# S7CAS-PLEIADES-CARTE-MERE_Pxx_FPGA_bank0.net
KiCad netlist of a schematic drawn in Altium Designer
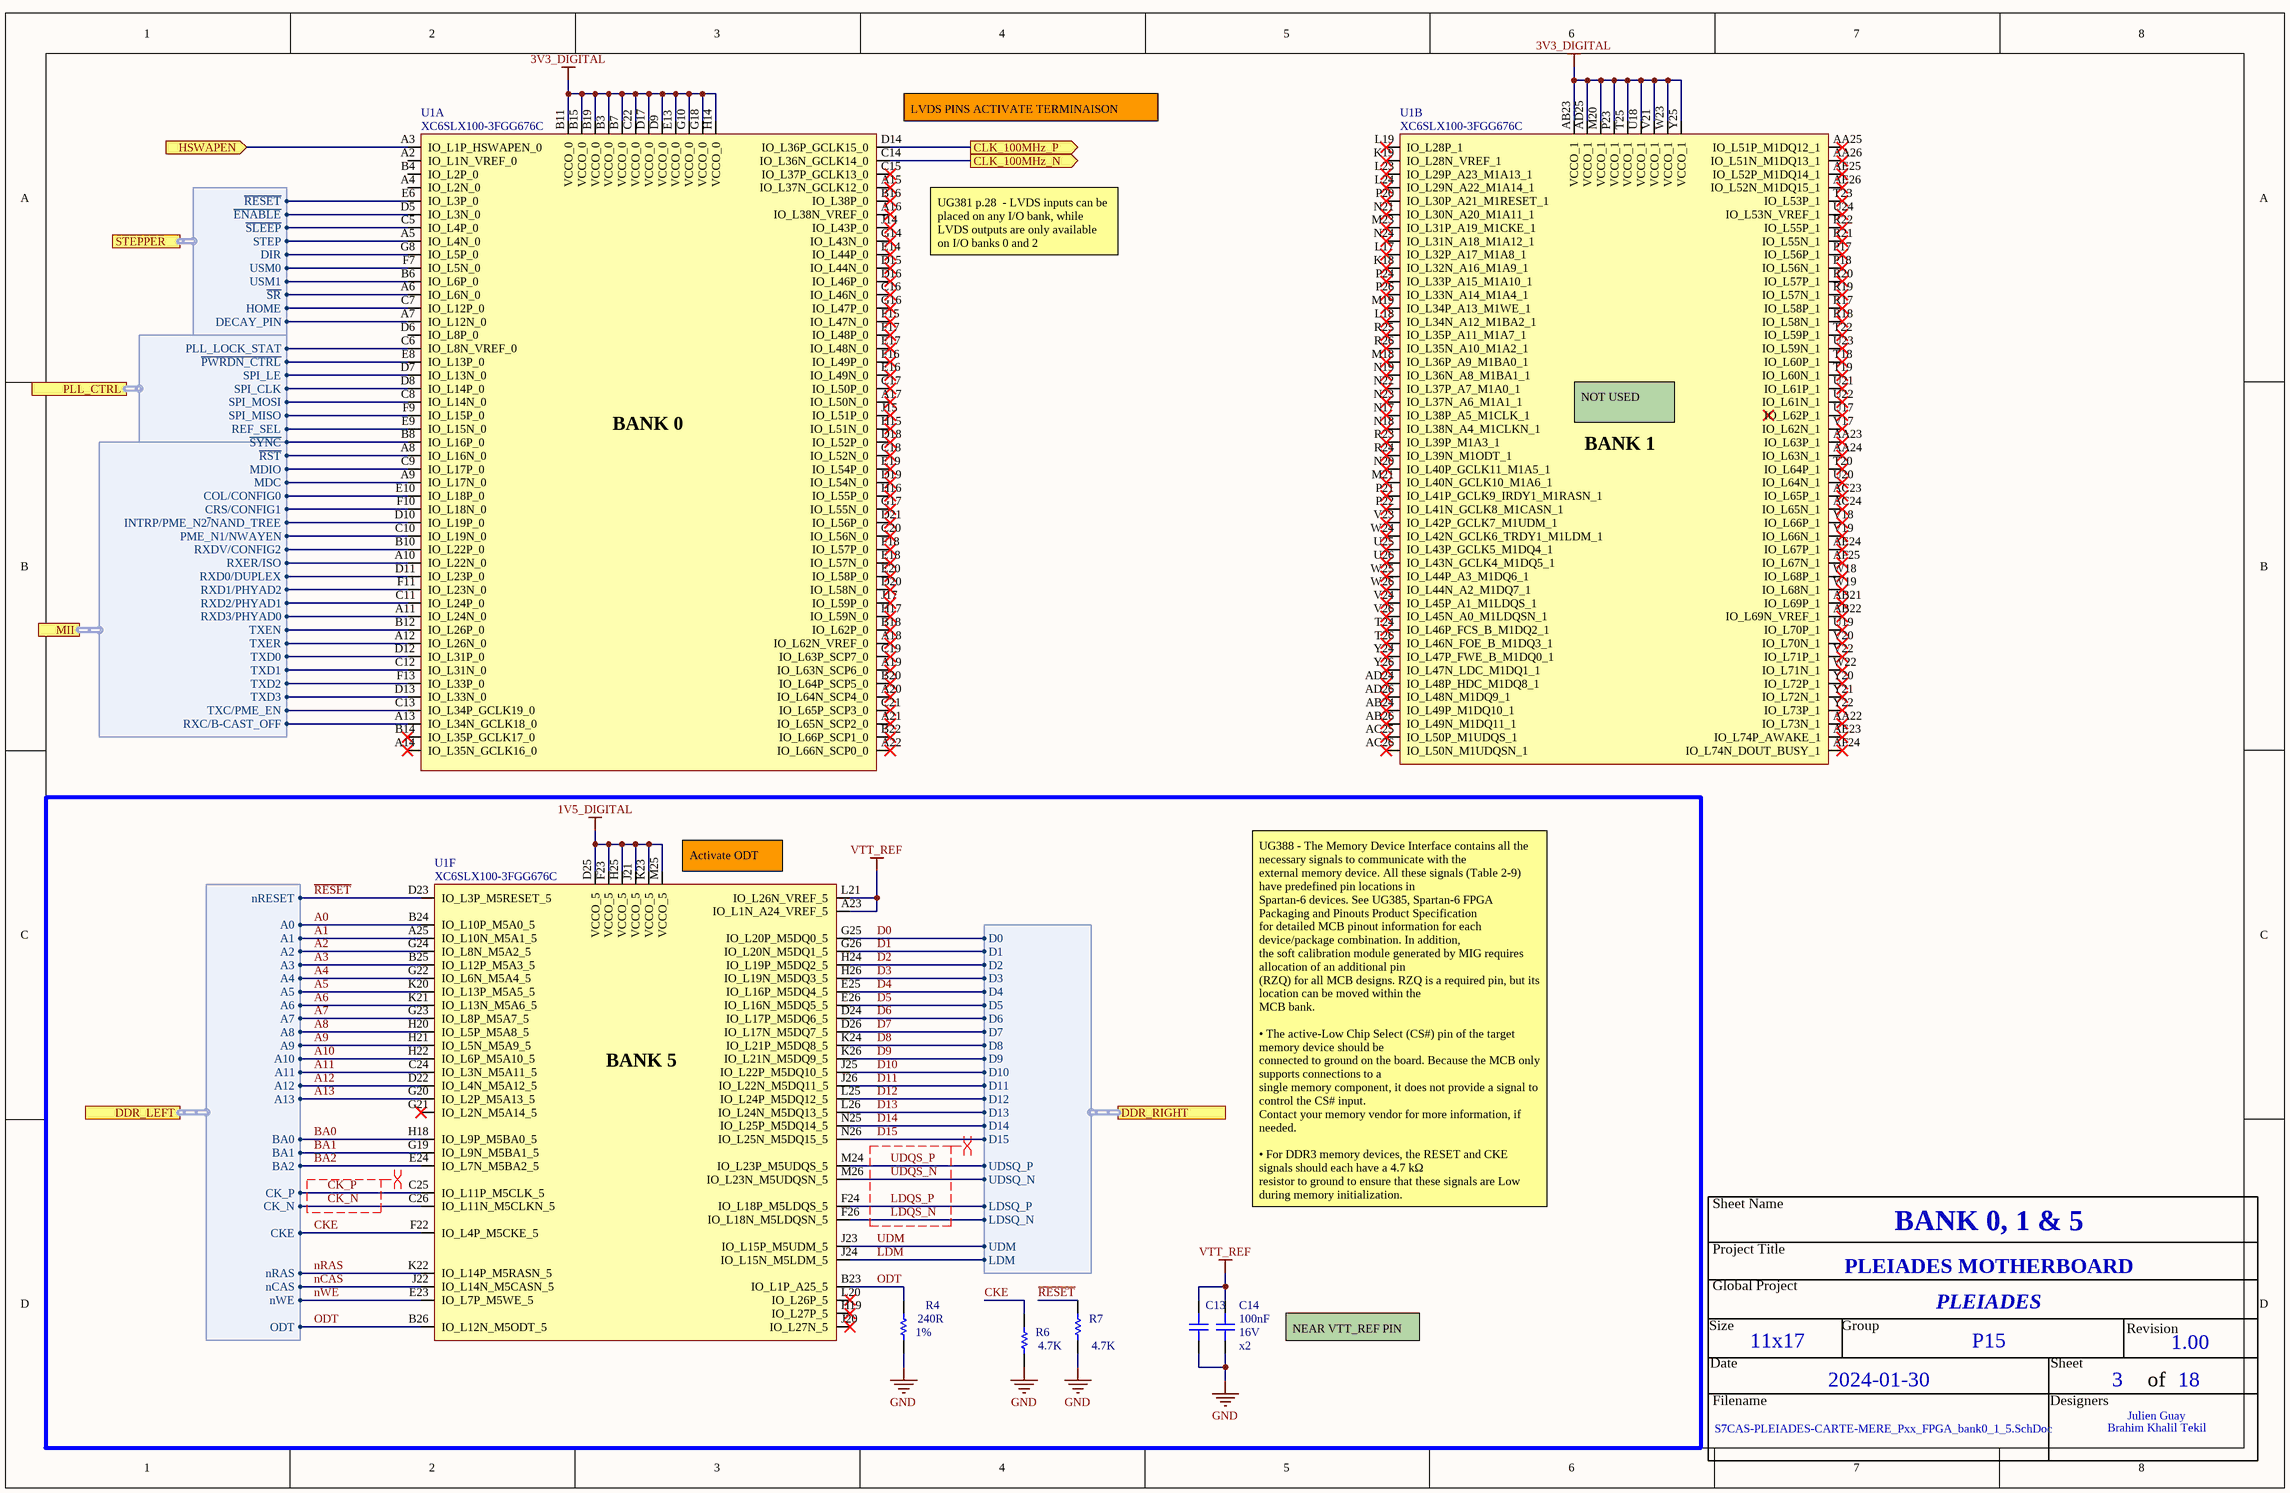
[diagram p0: S7CAS-PLEIADES-CARTE-MERE_Pxx_FPGA_bank0_1_5.SchDoc]

(export (version "E")
  (design (tool "Eeschema 10.0.6"))
  (components
    (comp (ref "C13")
      (value "CAP - 0603")
      (footprint "CAP_0603")
      (fields (field (name "VOLTAGE") "16V") (field (name "CREATEDBY") "Jonathan Bouchard"))
      (libsource (lib "S7CAS_LIB2023") (part "CAP - 0603"))
    )
    (comp (ref "C14")
      (value "100nF")
      (footprint "CAP_0603")
      (description "CAP - 0603")
      (fields (field (name "VOLTAGE") "16V") (field (name "CREATEDBY") "Jonathan Bouchard"))
      (libsource (lib "S7CAS_LIB2023") (part "CAP - 0603"))
    )
    (comp (ref "R4")
      (value "240R")
      (footprint "RES_0603")
      (description "RES - 0603")
      (fields (field (name "PRECISION") "1%") (field (name "CREATEDBY") "Jonathan Bouchard"))
      (libsource (lib "S7CAS_LIB2023") (part "RES - 0603"))
    )
    (comp (ref "R6")
      (value "4.7K")
      (footprint "RES_0603")
      (description "RES - 0603")
      (fields (field (name "CREATEDBY") "Jonathan Bouchard"))
      (libsource (lib "S7CAS_LIB2023") (part "RES - 0603"))
    )
    (comp (ref "R7")
      (value "4.7K")
      (footprint "RES_0603")
      (description "RES - 0603")
      (fields (field (name "CREATEDBY") "Jonathan Bouchard"))
      (libsource (lib "S7CAS_LIB2023") (part "RES - 0603"))
    )
    (comp (ref "U1")
      (value "XC6SLX100-3FGG676C")
      (footprint "FPGA_XILINX_FGG676")
      (description "FPGA - XILINX SPARTAN 6 480 I/O - BGA-676")
      (fields
        (field (name "VOLTAGE") "1.14 V ~ 1.26 V")
        (field (name "MFG") "Xilinx")
        (field (name "CREATEDBY") "Jonathan Bouchard")
      )
      (libsource (lib "S7CAS_LIB2023") (part "FPGA_XC6SLX100-3FGG676C"))
    )
  )
  (nets
    (net (code "9") (name "/A0") (class "Default")
      (node (ref "U1") (pin "B24") (pinfunction "IO_L10P_M5A0_5_B24") (pintype "passive"))
    )
    (net (code "10") (name "/A1") (class "Default")
      (node (ref "U1") (pin "A25") (pinfunction "IO_L10N_M5A1_5_A25") (pintype "passive"))
    )
    (net (code "11") (name "/A2") (class "Default")
      (node (ref "U1") (pin "G24") (pinfunction "IO_L8N_M5A2_5_G24") (pintype "passive"))
    )
    (net (code "12") (name "/A3") (class "Default")
      (node (ref "U1") (pin "B25") (pinfunction "IO_L12P_M5A3_5_B25") (pintype "passive"))
    )
    (net (code "13") (name "/A4") (class "Default")
      (node (ref "U1") (pin "G22") (pinfunction "IO_L6N_M5A4_5_G22") (pintype "passive"))
    )
    (net (code "14") (name "/A5") (class "Default")
      (node (ref "U1") (pin "K20") (pinfunction "IO_L13P_M5A5_5_K20") (pintype "passive"))
    )
    (net (code "15") (name "/A6") (class "Default")
      (node (ref "U1") (pin "K21") (pinfunction "IO_L13N_M5A6_5_K21") (pintype "passive"))
    )
    (net (code "16") (name "/A7") (class "Default")
      (node (ref "U1") (pin "G23") (pinfunction "IO_L8P_M5A7_5_G23") (pintype "passive"))
    )
    (net (code "17") (name "/A8") (class "Default")
      (node (ref "U1") (pin "H20") (pinfunction "IO_L5P_M5A8_5_H20") (pintype "passive"))
    )
    (net (code "18") (name "/A9") (class "Default")
      (node (ref "U1") (pin "H21") (pinfunction "IO_L5N_M5A9_5_H21") (pintype "passive"))
    )
    (net (code "19") (name "/A10") (class "Default")
      (node (ref "U1") (pin "H22") (pinfunction "IO_L6P_M5A10_5_H22") (pintype "passive"))
    )
    (net (code "20") (name "/A11") (class "Default")
      (node (ref "U1") (pin "C24") (pinfunction "IO_L3N_M5A11_5_C24") (pintype "passive"))
    )
    (net (code "21") (name "/A12") (class "Default")
      (node (ref "U1") (pin "D22") (pinfunction "IO_L4N_M5A12_5_D22") (pintype "passive"))
    )
    (net (code "22") (name "/A13") (class "Default")
      (node (ref "U1") (pin "G20") (pinfunction "IO_L2P_M5A13_5_G20") (pintype "passive"))
    )
    (net (code "23") (name "/BA0") (class "Default")
      (node (ref "U1") (pin "H18") (pinfunction "IO_L9P_M5BA0_5_H18") (pintype "passive"))
    )
    (net (code "24") (name "/BA1") (class "Default")
      (node (ref "U1") (pin "G19") (pinfunction "IO_L9N_M5BA1_5_G19") (pintype "passive"))
    )
    (net (code "25") (name "/BA2") (class "Default")
      (node (ref "U1") (pin "E24") (pinfunction "IO_L7N_M5BA2_5_E24") (pintype "passive"))
    )
    (net (code "26") (name "/CKE") (class "Default")
      (node (ref "R6") (pin "2") (pinfunction "2_2") (pintype "passive"))
      (node (ref "U1") (pin "F22") (pinfunction "IO_L4P_M5CKE_5_F22") (pintype "passive"))
    )
    (net (code "27") (name "/CK_N") (class "Default")
      (node (ref "U1") (pin "C26") (pinfunction "IO_L11N_M5CLKN_5_C26") (pintype "passive"))
    )
    (net (code "28") (name "/CK_P") (class "Default")
      (node (ref "U1") (pin "C25") (pinfunction "IO_L11P_M5CLK_5_C25") (pintype "passive"))
    )
    (net (code "29") (name "/CLK_100MHz_N") (class "Default")
      (node (ref "U1") (pin "C14") (pinfunction "IO_L36N_GCLK14_0_C14") (pintype "passive"))
    )
    (net (code "30") (name "/CLK_100MHz_P") (class "Default")
      (node (ref "U1") (pin "D14") (pinfunction "IO_L36P_GCLK15_0_D14") (pintype "passive"))
    )
    (net (code "31") (name "/D0") (class "Default")
      (node (ref "U1") (pin "G25") (pinfunction "IO_L20P_M5DQ0_5_G25") (pintype "passive"))
    )
    (net (code "32") (name "/D1") (class "Default")
      (node (ref "U1") (pin "G26") (pinfunction "IO_L20N_M5DQ1_5_G26") (pintype "passive"))
    )
    (net (code "33") (name "/D2") (class "Default")
      (node (ref "U1") (pin "H24") (pinfunction "IO_L19P_M5DQ2_5_H24") (pintype "passive"))
    )
    (net (code "34") (name "/D3") (class "Default")
      (node (ref "U1") (pin "H26") (pinfunction "IO_L19N_M5DQ3_5_H26") (pintype "passive"))
    )
    (net (code "35") (name "/D4") (class "Default")
      (node (ref "U1") (pin "E25") (pinfunction "IO_L16P_M5DQ4_5_E25") (pintype "passive"))
    )
    (net (code "36") (name "/D5") (class "Default")
      (node (ref "U1") (pin "E26") (pinfunction "IO_L16N_M5DQ5_5_E26") (pintype "passive"))
    )
    (net (code "37") (name "/D6") (class "Default")
      (node (ref "U1") (pin "D24") (pinfunction "IO_L17P_M5DQ6_5_D24") (pintype "passive"))
    )
    (net (code "38") (name "/D7") (class "Default")
      (node (ref "U1") (pin "D26") (pinfunction "IO_L17N_M5DQ7_5_D26") (pintype "passive"))
    )
    (net (code "39") (name "/D8") (class "Default")
      (node (ref "U1") (pin "K24") (pinfunction "IO_L21P_M5DQ8_5_K24") (pintype "passive"))
    )
    (net (code "40") (name "/D9") (class "Default")
      (node (ref "U1") (pin "K26") (pinfunction "IO_L21N_M5DQ9_5_K26") (pintype "passive"))
    )
    (net (code "41") (name "/D10") (class "Default")
      (node (ref "U1") (pin "J25") (pinfunction "IO_L22P_M5DQ10_5_J25") (pintype "passive"))
    )
    (net (code "42") (name "/D11") (class "Default")
      (node (ref "U1") (pin "J26") (pinfunction "IO_L22N_M5DQ11_5_J26") (pintype "passive"))
    )
    (net (code "43") (name "/D12") (class "Default")
      (node (ref "U1") (pin "L25") (pinfunction "IO_L24P_M5DQ12_5_L25") (pintype "passive"))
    )
    (net (code "44") (name "/D13") (class "Default")
      (node (ref "U1") (pin "L26") (pinfunction "IO_L24N_M5DQ13_5_L26") (pintype "passive"))
    )
    (net (code "45") (name "/D14") (class "Default")
      (node (ref "U1") (pin "N25") (pinfunction "IO_L25P_M5DQ14_5_N25") (pintype "passive"))
    )
    (net (code "46") (name "/D15") (class "Default")
      (node (ref "U1") (pin "N26") (pinfunction "IO_L25N_M5DQ15_5_N26") (pintype "passive"))
    )
    (net (code "47") (name "/HSWAPEN") (class "Default")
      (node (ref "U1") (pin "A3") (pinfunction "IO_L1P_HSWAPEN_0_A3") (pintype "passive"))
    )
    (net (code "48") (name "/LDM") (class "Default")
      (node (ref "U1") (pin "J24") (pinfunction "IO_L15N_M5LDM_5_J24") (pintype "passive"))
    )
    (net (code "49") (name "/LDQS_N") (class "Default")
      (node (ref "U1") (pin "F26") (pinfunction "IO_L18N_M5LDQSN_5_F26") (pintype "passive"))
    )
    (net (code "50") (name "/LDQS_P") (class "Default")
      (node (ref "U1") (pin "F24") (pinfunction "IO_L18P_M5LDQS_5_F24") (pintype "passive"))
    )
    (net (code "51") (name "/ODT") (class "Default")
      (node (ref "R4") (pin "2") (pinfunction "2_2") (pintype "passive"))
      (node (ref "U1") (pin "B23") (pinfunction "IO_L1P_A25_5_B23") (pintype "passive"))
      (node (ref "U1") (pin "B26") (pinfunction "IO_L12N_M5ODT_5_B26") (pintype "passive"))
    )
    (net (code "53") (name "/RESET") (class "Default")
      (node (ref "R7") (pin "2") (pinfunction "2_2") (pintype "passive"))
      (node (ref "U1") (pin "D23") (pinfunction "IO_L3P_M5RESET_5_D23") (pintype "passive"))
    )
    (net (code "55") (name "/UDM") (class "Default")
      (node (ref "U1") (pin "J23") (pinfunction "IO_L15P_M5UDM_5_J23") (pintype "passive"))
    )
    (net (code "56") (name "/UDQS_N") (class "Default")
      (node (ref "U1") (pin "M26") (pinfunction "IO_L23N_M5UDQSN_5_M26") (pintype "passive"))
    )
    (net (code "57") (name "/UDQS_P") (class "Default")
      (node (ref "U1") (pin "M24") (pinfunction "IO_L23P_M5UDQS_5_M24") (pintype "passive"))
    )
    (net (code "58") (name "/nCAS") (class "Default")
      (node (ref "U1") (pin "J22") (pinfunction "IO_L14N_M5CASN_5_J22") (pintype "passive"))
    )
    (net (code "59") (name "/nRAS") (class "Default")
      (node (ref "U1") (pin "K22") (pinfunction "IO_L14P_M5RASN_5_K22") (pintype "passive"))
    )
    (net (code "60") (name "/nWE") (class "Default")
      (node (ref "U1") (pin "E23") (pinfunction "IO_L7P_M5WE_5_E23") (pintype "passive"))
    )
    (net (code "64") (name "1V5_DIGITAL") (class "Default")
      (node (ref "U1") (pin "D25") (pinfunction "VCCO_5_D25") (pintype "passive"))
      (node (ref "U1") (pin "F23") (pinfunction "VCCO_5_F23") (pintype "passive"))
      (node (ref "U1") (pin "H25") (pinfunction "VCCO_5_H25") (pintype "passive"))
      (node (ref "U1") (pin "J21") (pinfunction "VCCO_5_J21") (pintype "passive"))
      (node (ref "U1") (pin "K23") (pinfunction "VCCO_5_K23") (pintype "passive"))
      (node (ref "U1") (pin "M25") (pinfunction "VCCO_5_M25") (pintype "passive"))
    )
    (net (code "65") (name "3V3_DIGITAL") (class "Default")
      (node (ref "U1") (pin "AB23") (pinfunction "VCCO_1_AB23") (pintype "passive"))
      (node (ref "U1") (pin "AD25") (pinfunction "VCCO_1_AD25") (pintype "passive"))
      (node (ref "U1") (pin "B11") (pinfunction "VCCO_0_B11") (pintype "passive"))
      (node (ref "U1") (pin "B15") (pinfunction "VCCO_0_B15") (pintype "passive"))
      (node (ref "U1") (pin "B19") (pinfunction "VCCO_0_B19") (pintype "passive"))
      (node (ref "U1") (pin "B3") (pinfunction "VCCO_0_B3") (pintype "passive"))
      (node (ref "U1") (pin "B7") (pinfunction "VCCO_0_B7") (pintype "passive"))
      (node (ref "U1") (pin "C22") (pinfunction "VCCO_0_C22") (pintype "passive"))
      (node (ref "U1") (pin "D17") (pinfunction "VCCO_0_D17") (pintype "passive"))
      (node (ref "U1") (pin "D9") (pinfunction "VCCO_0_D9") (pintype "passive"))
      (node (ref "U1") (pin "E13") (pinfunction "VCCO_0_E13") (pintype "passive"))
      (node (ref "U1") (pin "G10") (pinfunction "VCCO_0_G10") (pintype "passive"))
      (node (ref "U1") (pin "G18") (pinfunction "VCCO_0_G18") (pintype "passive"))
      (node (ref "U1") (pin "H14") (pinfunction "VCCO_0_H14") (pintype "passive"))
      (node (ref "U1") (pin "M20") (pinfunction "VCCO_1_M20") (pintype "passive"))
      (node (ref "U1") (pin "P23") (pinfunction "VCCO_1_P23") (pintype "passive"))
      (node (ref "U1") (pin "T25") (pinfunction "VCCO_1_T25") (pintype "passive"))
      (node (ref "U1") (pin "U18") (pinfunction "VCCO_1_U18") (pintype "passive"))
      (node (ref "U1") (pin "V21") (pinfunction "VCCO_1_V21") (pintype "passive"))
      (node (ref "U1") (pin "W23") (pinfunction "VCCO_1_W23") (pintype "passive"))
      (node (ref "U1") (pin "Y25") (pinfunction "VCCO_1_Y25") (pintype "passive"))
    )
    (net (code "66") (name "GND") (class "Default")
      (node (ref "C13") (pin "1") (pinfunction "1_1") (pintype "passive"))
      (node (ref "C14") (pin "1") (pinfunction "1_1") (pintype "passive"))
      (node (ref "R4") (pin "1") (pinfunction "1_1") (pintype "passive"))
      (node (ref "R6") (pin "1") (pinfunction "1_1") (pintype "passive"))
      (node (ref "R7") (pin "1") (pinfunction "1_1") (pintype "passive"))
    )
    (net (code "67") (name "VTT_REF") (class "Default")
      (node (ref "C13") (pin "2") (pinfunction "2_2") (pintype "passive"))
      (node (ref "C14") (pin "2") (pinfunction "2_2") (pintype "passive"))
      (node (ref "U1") (pin "A23") (pinfunction "IO_L1N_A24_VREF_5_A23") (pintype "passive"))
      (node (ref "U1") (pin "L21") (pinfunction "IO_L26N_VREF_5_L21") (pintype "passive"))
    )
    (net (code "68") (name "unconnected-(U1A-IO_L1N_VREF_0-PadA2)") (class "Default")
      (node (ref "U1") (pin "A2") (pinfunction "IO_L1N_VREF_0_A2") (pintype "passive"))
    )
    (net (code "69") (name "unconnected-(U1A-IO_L2N_0-PadA4)") (class "Default")
      (node (ref "U1") (pin "A4") (pinfunction "IO_L2N_0_A4") (pintype "passive"))
    )
    (net (code "70") (name "unconnected-(U1A-IO_L2P_0-PadB4)") (class "Default")
      (node (ref "U1") (pin "B4") (pinfunction "IO_L2P_0_B4") (pintype "passive"))
    )
    (net (code "71") (name "unconnected-(U1A-IO_L3N_0-PadD5)") (class "Default")
      (node (ref "U1") (pin "D5") (pinfunction "IO_L3N_0_D5") (pintype "passive"))
    )
    (net (code "72") (name "unconnected-(U1A-IO_L3P_0-PadE6)") (class "Default")
      (node (ref "U1") (pin "E6") (pinfunction "IO_L3P_0_E6") (pintype "passive"))
    )
    (net (code "73") (name "unconnected-(U1A-IO_L4N_0-PadA5)") (class "Default")
      (node (ref "U1") (pin "A5") (pinfunction "IO_L4N_0_A5") (pintype "passive"))
    )
    (net (code "74") (name "unconnected-(U1A-IO_L4P_0-PadC5)") (class "Default")
      (node (ref "U1") (pin "C5") (pinfunction "IO_L4P_0_C5") (pintype "passive"))
    )
    (net (code "75") (name "unconnected-(U1A-IO_L5N_0-PadF7)") (class "Default")
      (node (ref "U1") (pin "F7") (pinfunction "IO_L5N_0_F7") (pintype "passive"))
    )
    (net (code "76") (name "unconnected-(U1A-IO_L5P_0-PadG8)") (class "Default")
      (node (ref "U1") (pin "G8") (pinfunction "IO_L5P_0_G8") (pintype "passive"))
    )
    (net (code "77") (name "unconnected-(U1A-IO_L6N_0-PadA6)") (class "Default")
      (node (ref "U1") (pin "A6") (pinfunction "IO_L6N_0_A6") (pintype "passive"))
    )
    (net (code "78") (name "unconnected-(U1A-IO_L6P_0-PadB6)") (class "Default")
      (node (ref "U1") (pin "B6") (pinfunction "IO_L6P_0_B6") (pintype "passive"))
    )
    (net (code "79") (name "unconnected-(U1A-IO_L8N_VREF_0-PadC6)") (class "Default")
      (node (ref "U1") (pin "C6") (pinfunction "IO_L8N_VREF_0_C6") (pintype "passive"))
    )
    (net (code "80") (name "unconnected-(U1A-IO_L8P_0-PadD6)") (class "Default")
      (node (ref "U1") (pin "D6") (pinfunction "IO_L8P_0_D6") (pintype "passive"))
    )
    (net (code "81") (name "unconnected-(U1A-IO_L12N_0-PadA7)") (class "Default")
      (node (ref "U1") (pin "A7") (pinfunction "IO_L12N_0_A7") (pintype "passive"))
    )
    (net (code "82") (name "unconnected-(U1A-IO_L12P_0-PadC7)") (class "Default")
      (node (ref "U1") (pin "C7") (pinfunction "IO_L12P_0_C7") (pintype "passive"))
    )
    (net (code "83") (name "unconnected-(U1A-IO_L13N_0-PadD7)") (class "Default")
      (node (ref "U1") (pin "D7") (pinfunction "IO_L13N_0_D7") (pintype "passive"))
    )
    (net (code "84") (name "unconnected-(U1A-IO_L13P_0-PadE8)") (class "Default")
      (node (ref "U1") (pin "E8") (pinfunction "IO_L13P_0_E8") (pintype "passive"))
    )
    (net (code "85") (name "unconnected-(U1A-IO_L14N_0-PadC8)") (class "Default")
      (node (ref "U1") (pin "C8") (pinfunction "IO_L14N_0_C8") (pintype "passive"))
    )
    (net (code "86") (name "unconnected-(U1A-IO_L14P_0-PadD8)") (class "Default")
      (node (ref "U1") (pin "D8") (pinfunction "IO_L14P_0_D8") (pintype "passive"))
    )
    (net (code "87") (name "unconnected-(U1A-IO_L15N_0-PadE9)") (class "Default")
      (node (ref "U1") (pin "E9") (pinfunction "IO_L15N_0_E9") (pintype "passive"))
    )
    (net (code "88") (name "unconnected-(U1A-IO_L15P_0-PadF9)") (class "Default")
      (node (ref "U1") (pin "F9") (pinfunction "IO_L15P_0_F9") (pintype "passive"))
    )
    (net (code "89") (name "unconnected-(U1A-IO_L16N_0-PadA8)") (class "Default")
      (node (ref "U1") (pin "A8") (pinfunction "IO_L16N_0_A8") (pintype "passive"))
    )
    (net (code "90") (name "unconnected-(U1A-IO_L16P_0-PadB8)") (class "Default")
      (node (ref "U1") (pin "B8") (pinfunction "IO_L16P_0_B8") (pintype "passive"))
    )
    (net (code "91") (name "unconnected-(U1A-IO_L17N_0-PadA9)") (class "Default")
      (node (ref "U1") (pin "A9") (pinfunction "IO_L17N_0_A9") (pintype "passive"))
    )
    (net (code "92") (name "unconnected-(U1A-IO_L17P_0-PadC9)") (class "Default")
      (node (ref "U1") (pin "C9") (pinfunction "IO_L17P_0_C9") (pintype "passive"))
    )
    (net (code "93") (name "unconnected-(U1A-IO_L18N_0-PadF10)") (class "Default")
      (node (ref "U1") (pin "F10") (pinfunction "IO_L18N_0_F10") (pintype "passive"))
    )
    (net (code "94") (name "unconnected-(U1A-IO_L18P_0-PadE10)") (class "Default")
      (node (ref "U1") (pin "E10") (pinfunction "IO_L18P_0_E10") (pintype "passive"))
    )
    (net (code "95") (name "unconnected-(U1A-IO_L19N_0-PadC10)") (class "Default")
      (node (ref "U1") (pin "C10") (pinfunction "IO_L19N_0_C10") (pintype "passive"))
    )
    (net (code "96") (name "unconnected-(U1A-IO_L19P_0-PadD10)") (class "Default")
      (node (ref "U1") (pin "D10") (pinfunction "IO_L19P_0_D10") (pintype "passive"))
    )
    (net (code "97") (name "unconnected-(U1A-IO_L22N_0-PadA10)") (class "Default")
      (node (ref "U1") (pin "A10") (pinfunction "IO_L22N_0_A10") (pintype "passive"))
    )
    (net (code "98") (name "unconnected-(U1A-IO_L22P_0-PadB10)") (class "Default")
      (node (ref "U1") (pin "B10") (pinfunction "IO_L22P_0_B10") (pintype "passive"))
    )
    (net (code "99") (name "unconnected-(U1A-IO_L23N_0-PadF11)") (class "Default")
      (node (ref "U1") (pin "F11") (pinfunction "IO_L23N_0_F11") (pintype "passive"))
    )
    (net (code "100") (name "unconnected-(U1A-IO_L23P_0-PadD11)") (class "Default")
      (node (ref "U1") (pin "D11") (pinfunction "IO_L23P_0_D11") (pintype "passive"))
    )
    (net (code "101") (name "unconnected-(U1A-IO_L24N_0-PadA11)") (class "Default")
      (node (ref "U1") (pin "A11") (pinfunction "IO_L24N_0_A11") (pintype "passive"))
    )
    (net (code "102") (name "unconnected-(U1A-IO_L24P_0-PadC11)") (class "Default")
      (node (ref "U1") (pin "C11") (pinfunction "IO_L24P_0_C11") (pintype "passive"))
    )
    (net (code "103") (name "unconnected-(U1A-IO_L26N_0-PadA12)") (class "Default")
      (node (ref "U1") (pin "A12") (pinfunction "IO_L26N_0_A12") (pintype "passive"))
    )
    (net (code "104") (name "unconnected-(U1A-IO_L26P_0-PadB12)") (class "Default")
      (node (ref "U1") (pin "B12") (pinfunction "IO_L26P_0_B12") (pintype "passive"))
    )
    (net (code "105") (name "unconnected-(U1A-IO_L31N_0-PadC12)") (class "Default")
      (node (ref "U1") (pin "C12") (pinfunction "IO_L31N_0_C12") (pintype "passive"))
    )
    (net (code "106") (name "unconnected-(U1A-IO_L31P_0-PadD12)") (class "Default")
      (node (ref "U1") (pin "D12") (pinfunction "IO_L31P_0_D12") (pintype "passive"))
    )
    (net (code "107") (name "unconnected-(U1A-IO_L33N_0-PadD13)") (class "Default")
      (node (ref "U1") (pin "D13") (pinfunction "IO_L33N_0_D13") (pintype "passive"))
    )
    (net (code "108") (name "unconnected-(U1A-IO_L33P_0-PadF13)") (class "Default")
      (node (ref "U1") (pin "F13") (pinfunction "IO_L33P_0_F13") (pintype "passive"))
    )
    (net (code "109") (name "unconnected-(U1A-IO_L34N_GCLK18_0-PadA13)") (class "Default")
      (node (ref "U1") (pin "A13") (pinfunction "IO_L34N_GCLK18_0_A13") (pintype "passive"))
    )
    (net (code "110") (name "unconnected-(U1A-IO_L34P_GCLK19_0-PadC13)") (class "Default")
      (node (ref "U1") (pin "C13") (pinfunction "IO_L34P_GCLK19_0_C13") (pintype "passive"))
    )
    (net (code "111") (name "unconnected-(U1A-IO_L35N_GCLK16_0-PadA14)") (class "Default")
      (node (ref "U1") (pin "A14") (pinfunction "IO_L35N_GCLK16_0_A14") (pintype "passive+no_connect"))
    )
    (net (code "112") (name "unconnected-(U1A-IO_L35P_GCLK17_0-PadB14)") (class "Default")
      (node (ref "U1") (pin "B14") (pinfunction "IO_L35P_GCLK17_0_B14") (pintype "passive+no_connect"))
    )
    (net (code "113") (name "unconnected-(U1A-IO_L37N_GCLK12_0-PadA15)") (class "Default")
      (node (ref "U1") (pin "A15") (pinfunction "IO_L37N_GCLK12_0_A15") (pintype "passive+no_connect"))
    )
    (net (code "114") (name "unconnected-(U1A-IO_L37P_GCLK13_0-PadC15)") (class "Default")
      (node (ref "U1") (pin "C15") (pinfunction "IO_L37P_GCLK13_0_C15") (pintype "passive+no_connect"))
    )
    (net (code "115") (name "unconnected-(U1A-IO_L38N_VREF_0-PadA16)") (class "Default")
      (node (ref "U1") (pin "A16") (pinfunction "IO_L38N_VREF_0_A16") (pintype "passive+no_connect"))
    )
    (net (code "116") (name "unconnected-(U1A-IO_L38P_0-PadB16)") (class "Default")
      (node (ref "U1") (pin "B16") (pinfunction "IO_L38P_0_B16") (pintype "passive+no_connect"))
    )
    (net (code "117") (name "unconnected-(U1A-IO_L43N_0-PadG14)") (class "Default")
      (node (ref "U1") (pin "G14") (pinfunction "IO_L43N_0_G14") (pintype "passive+no_connect"))
    )
    (net (code "118") (name "unconnected-(U1A-IO_L43P_0-PadJ14)") (class "Default")
      (node (ref "U1") (pin "J14") (pinfunction "IO_L43P_0_J14") (pintype "passive+no_connect"))
    )
    (net (code "119") (name "unconnected-(U1A-IO_L44N_0-PadD15)") (class "Default")
      (node (ref "U1") (pin "D15") (pinfunction "IO_L44N_0_D15") (pintype "passive+no_connect"))
    )
    (net (code "120") (name "unconnected-(U1A-IO_L44P_0-PadE14)") (class "Default")
      (node (ref "U1") (pin "E14") (pinfunction "IO_L44P_0_E14") (pintype "passive+no_connect"))
    )
    (net (code "121") (name "unconnected-(U1A-IO_L46N_0-PadC16)") (class "Default")
      (node (ref "U1") (pin "C16") (pinfunction "IO_L46N_0_C16") (pintype "passive+no_connect"))
    )
    (net (code "122") (name "unconnected-(U1A-IO_L46P_0-PadD16)") (class "Default")
      (node (ref "U1") (pin "D16") (pinfunction "IO_L46P_0_D16") (pintype "passive+no_connect"))
    )
    (net (code "123") (name "unconnected-(U1A-IO_L47N_0-PadF15)") (class "Default")
      (node (ref "U1") (pin "F15") (pinfunction "IO_L47N_0_F15") (pintype "passive+no_connect"))
    )
    (net (code "124") (name "unconnected-(U1A-IO_L47P_0-PadG16)") (class "Default")
      (node (ref "U1") (pin "G16") (pinfunction "IO_L47P_0_G16") (pintype "passive+no_connect"))
    )
    (net (code "125") (name "unconnected-(U1A-IO_L48N_0-PadE17)") (class "Default")
      (node (ref "U1") (pin "E17") (pinfunction "IO_L48N_0_E17") (pintype "passive+no_connect"))
    )
    (net (code "126") (name "unconnected-(U1A-IO_L48P_0-PadF17)") (class "Default")
      (node (ref "U1") (pin "F17") (pinfunction "IO_L48P_0_F17") (pintype "passive+no_connect"))
    )
    (net (code "127") (name "unconnected-(U1A-IO_L49N_0-PadE16)") (class "Default")
      (node (ref "U1") (pin "E16") (pinfunction "IO_L49N_0_E16") (pintype "passive+no_connect"))
    )
    (net (code "128") (name "unconnected-(U1A-IO_L49P_0-PadF16)") (class "Default")
      (node (ref "U1") (pin "F16") (pinfunction "IO_L49P_0_F16") (pintype "passive+no_connect"))
    )
    (net (code "129") (name "unconnected-(U1A-IO_L50N_0-PadA17)") (class "Default")
      (node (ref "U1") (pin "A17") (pinfunction "IO_L50N_0_A17") (pintype "passive+no_connect"))
    )
    (net (code "130") (name "unconnected-(U1A-IO_L50P_0-PadC17)") (class "Default")
      (node (ref "U1") (pin "C17") (pinfunction "IO_L50P_0_C17") (pintype "passive+no_connect"))
    )
    (net (code "131") (name "unconnected-(U1A-IO_L51N_0-PadH15)") (class "Default")
      (node (ref "U1") (pin "H15") (pinfunction "IO_L51N_0_H15") (pintype "passive+no_connect"))
    )
    (net (code "132") (name "unconnected-(U1A-IO_L51P_0-PadJ15)") (class "Default")
      (node (ref "U1") (pin "J15") (pinfunction "IO_L51P_0_J15") (pintype "passive+no_connect"))
    )
    (net (code "133") (name "unconnected-(U1A-IO_L52N_0-PadC18)") (class "Default")
      (node (ref "U1") (pin "C18") (pinfunction "IO_L52N_0_C18") (pintype "passive+no_connect"))
    )
    (net (code "134") (name "unconnected-(U1A-IO_L52P_0-PadD18)") (class "Default")
      (node (ref "U1") (pin "D18") (pinfunction "IO_L52P_0_D18") (pintype "passive+no_connect"))
    )
    (net (code "135") (name "unconnected-(U1A-IO_L54N_0-PadD19)") (class "Default")
      (node (ref "U1") (pin "D19") (pinfunction "IO_L54N_0_D19") (pintype "passive+no_connect"))
    )
    (net (code "136") (name "unconnected-(U1A-IO_L54P_0-PadE19)") (class "Default")
      (node (ref "U1") (pin "E19") (pinfunction "IO_L54P_0_E19") (pintype "passive+no_connect"))
    )
    (net (code "137") (name "unconnected-(U1A-IO_L55N_0-PadG17)") (class "Default")
      (node (ref "U1") (pin "G17") (pinfunction "IO_L55N_0_G17") (pintype "passive+no_connect"))
    )
    (net (code "138") (name "unconnected-(U1A-IO_L55P_0-PadH16)") (class "Default")
      (node (ref "U1") (pin "H16") (pinfunction "IO_L55P_0_H16") (pintype "passive+no_connect"))
    )
    (net (code "139") (name "unconnected-(U1A-IO_L56N_0-PadC20)") (class "Default")
      (node (ref "U1") (pin "C20") (pinfunction "IO_L56N_0_C20") (pintype "passive+no_connect"))
    )
    (net (code "140") (name "unconnected-(U1A-IO_L56P_0-PadD21)") (class "Default")
      (node (ref "U1") (pin "D21") (pinfunction "IO_L56P_0_D21") (pintype "passive+no_connect"))
    )
    (net (code "141") (name "unconnected-(U1A-IO_L57N_0-PadE18)") (class "Default")
      (node (ref "U1") (pin "E18") (pinfunction "IO_L57N_0_E18") (pintype "passive+no_connect"))
    )
    (net (code "142") (name "unconnected-(U1A-IO_L57P_0-PadF18)") (class "Default")
      (node (ref "U1") (pin "F18") (pinfunction "IO_L57P_0_F18") (pintype "passive+no_connect"))
    )
    (net (code "143") (name "unconnected-(U1A-IO_L58N_0-PadD20)") (class "Default")
      (node (ref "U1") (pin "D20") (pinfunction "IO_L58N_0_D20") (pintype "passive+no_connect"))
    )
    (net (code "144") (name "unconnected-(U1A-IO_L58P_0-PadE20)") (class "Default")
      (node (ref "U1") (pin "E20") (pinfunction "IO_L58P_0_E20") (pintype "passive+no_connect"))
    )
    (net (code "145") (name "unconnected-(U1A-IO_L59N_0-PadH17)") (class "Default")
      (node (ref "U1") (pin "H17") (pinfunction "IO_L59N_0_H17") (pintype "passive+no_connect"))
    )
    (net (code "146") (name "unconnected-(U1A-IO_L59P_0-PadJ17)") (class "Default")
      (node (ref "U1") (pin "J17") (pinfunction "IO_L59P_0_J17") (pintype "passive+no_connect"))
    )
    (net (code "147") (name "unconnected-(U1A-IO_L62N_VREF_0-PadA18)") (class "Default")
      (node (ref "U1") (pin "A18") (pinfunction "IO_L62N_VREF_0_A18") (pintype "passive+no_connect"))
    )
    (net (code "148") (name "unconnected-(U1A-IO_L62P_0-PadB18)") (class "Default")
      (node (ref "U1") (pin "B18") (pinfunction "IO_L62P_0_B18") (pintype "passive+no_connect"))
    )
    (net (code "149") (name "unconnected-(U1A-IO_L63N_SCP6_0-PadA19)") (class "Default")
      (node (ref "U1") (pin "A19") (pinfunction "IO_L63N_SCP6_0_A19") (pintype "passive+no_connect"))
    )
    (net (code "150") (name "unconnected-(U1A-IO_L63P_SCP7_0-PadC19)") (class "Default")
      (node (ref "U1") (pin "C19") (pinfunction "IO_L63P_SCP7_0_C19") (pintype "passive+no_connect"))
    )
    (net (code "151") (name "unconnected-(U1A-IO_L64N_SCP4_0-PadA20)") (class "Default")
      (node (ref "U1") (pin "A20") (pinfunction "IO_L64N_SCP4_0_A20") (pintype "passive+no_connect"))
    )
    (net (code "152") (name "unconnected-(U1A-IO_L64P_SCP5_0-PadB20)") (class "Default")
      (node (ref "U1") (pin "B20") (pinfunction "IO_L64P_SCP5_0_B20") (pintype "passive+no_connect"))
    )
    (net (code "153") (name "unconnected-(U1A-IO_L65N_SCP2_0-PadA21)") (class "Default")
      (node (ref "U1") (pin "A21") (pinfunction "IO_L65N_SCP2_0_A21") (pintype "passive+no_connect"))
    )
    (net (code "154") (name "unconnected-(U1A-IO_L65P_SCP3_0-PadC21)") (class "Default")
      (node (ref "U1") (pin "C21") (pinfunction "IO_L65P_SCP3_0_C21") (pintype "passive+no_connect"))
    )
    (net (code "155") (name "unconnected-(U1A-IO_L66N_SCP0_0-PadA22)") (class "Default")
      (node (ref "U1") (pin "A22") (pinfunction "IO_L66N_SCP0_0_A22") (pintype "passive+no_connect"))
    )
    (net (code "156") (name "unconnected-(U1A-IO_L66P_SCP1_0-PadB22)") (class "Default")
      (node (ref "U1") (pin "B22") (pinfunction "IO_L66P_SCP1_0_B22") (pintype "passive+no_connect"))
    )
    (net (code "157") (name "unconnected-(U1B-IO_L28N_VREF_1-PadK19)") (class "Default")
      (node (ref "U1") (pin "K19") (pinfunction "IO_L28N_VREF_1_K19") (pintype "passive+no_connect"))
    )
    (net (code "158") (name "unconnected-(U1B-IO_L28P_1-PadL19)") (class "Default")
      (node (ref "U1") (pin "L19") (pinfunction "IO_L28P_1_L19") (pintype "passive+no_connect"))
    )
    (net (code "159") (name "unconnected-(U1B-IO_L29N_A22_M1A14_1-PadL24)") (class "Default")
      (node (ref "U1") (pin "L24") (pinfunction "IO_L29N_A22_M1A14_1_L24") (pintype "passive+no_connect"))
    )
    (net (code "160") (name "unconnected-(U1B-IO_L29P_A23_M1A13_1-PadL23)") (class "Default")
      (node (ref "U1") (pin "L23") (pinfunction "IO_L29P_A23_M1A13_1_L23") (pintype "passive+no_connect"))
    )
    (net (code "161") (name "unconnected-(U1B-IO_L30N_A20_M1A11_1-PadN21)") (class "Default")
      (node (ref "U1") (pin "N21") (pinfunction "IO_L30N_A20_M1A11_1_N21") (pintype "passive+no_connect"))
    )
    (net (code "162") (name "unconnected-(U1B-IO_L30P_A21_M1RESET_1-PadP20)") (class "Default")
      (node (ref "U1") (pin "P20") (pinfunction "IO_L30P_A21_M1RESET_1_P20") (pintype "passive+no_connect"))
    )
    (net (code "163") (name "unconnected-(U1B-IO_L31N_A18_M1A12_1-PadN24)") (class "Default")
      (node (ref "U1") (pin "N24") (pinfunction "IO_L31N_A18_M1A12_1_N24") (pintype "passive+no_connect"))
    )
    (net (code "164") (name "unconnected-(U1B-IO_L31P_A19_M1CKE_1-PadM23)") (class "Default")
      (node (ref "U1") (pin "M23") (pinfunction "IO_L31P_A19_M1CKE_1_M23") (pintype "passive+no_connect"))
    )
    (net (code "165") (name "unconnected-(U1B-IO_L32N_A16_M1A9_1-PadK18)") (class "Default")
      (node (ref "U1") (pin "K18") (pinfunction "IO_L32N_A16_M1A9_1_K18") (pintype "passive+no_connect"))
    )
    (net (code "166") (name "unconnected-(U1B-IO_L32P_A17_M1A8_1-PadL17)") (class "Default")
      (node (ref "U1") (pin "L17") (pinfunction "IO_L32P_A17_M1A8_1_L17") (pintype "passive+no_connect"))
    )
    (net (code "167") (name "unconnected-(U1B-IO_L33N_A14_M1A4_1-PadP26)") (class "Default")
      (node (ref "U1") (pin "P26") (pinfunction "IO_L33N_A14_M1A4_1_P26") (pintype "passive+no_connect"))
    )
    (net (code "168") (name "unconnected-(U1B-IO_L33P_A15_M1A10_1-PadP24)") (class "Default")
      (node (ref "U1") (pin "P24") (pinfunction "IO_L33P_A15_M1A10_1_P24") (pintype "passive+no_connect"))
    )
    (net (code "169") (name "unconnected-(U1B-IO_L34N_A12_M1BA2_1-PadL18)") (class "Default")
      (node (ref "U1") (pin "L18") (pinfunction "IO_L34N_A12_M1BA2_1_L18") (pintype "passive+no_connect"))
    )
    (net (code "170") (name "unconnected-(U1B-IO_L34P_A13_M1WE_1-PadM19)") (class "Default")
      (node (ref "U1") (pin "M19") (pinfunction "IO_L34P_A13_M1WE_1_M19") (pintype "passive+no_connect"))
    )
    (net (code "171") (name "unconnected-(U1B-IO_L35N_A10_M1A2_1-PadR26)") (class "Default")
      (node (ref "U1") (pin "R26") (pinfunction "IO_L35N_A10_M1A2_1_R26") (pintype "passive+no_connect"))
    )
    (net (code "172") (name "unconnected-(U1B-IO_L35P_A11_M1A7_1-PadR25)") (class "Default")
      (node (ref "U1") (pin "R25") (pinfunction "IO_L35P_A11_M1A7_1_R25") (pintype "passive+no_connect"))
    )
    (net (code "173") (name "unconnected-(U1B-IO_L36N_A8_M1BA1_1-PadN19)") (class "Default")
      (node (ref "U1") (pin "N19") (pinfunction "IO_L36N_A8_M1BA1_1_N19") (pintype "passive+no_connect"))
    )
    (net (code "174") (name "unconnected-(U1B-IO_L36P_A9_M1BA0_1-PadM18)") (class "Default")
      (node (ref "U1") (pin "M18") (pinfunction "IO_L36P_A9_M1BA0_1_M18") (pintype "passive+no_connect"))
    )
    (net (code "175") (name "unconnected-(U1B-IO_L37N_A6_M1A1_1-PadN23)") (class "Default")
      (node (ref "U1") (pin "N23") (pinfunction "IO_L37N_A6_M1A1_1_N23") (pintype "passive+no_connect"))
    )
    (net (code "176") (name "unconnected-(U1B-IO_L37P_A7_M1A0_1-PadN22)") (class "Default")
      (node (ref "U1") (pin "N22") (pinfunction "IO_L37P_A7_M1A0_1_N22") (pintype "passive+no_connect"))
    )
    (net (code "177") (name "unconnected-(U1B-IO_L38N_A4_M1CLKN_1-PadN18)") (class "Default")
      (node (ref "U1") (pin "N18") (pinfunction "IO_L38N_A4_M1CLKN_1_N18") (pintype "passive+no_connect"))
    )
    (net (code "178") (name "unconnected-(U1B-IO_L38P_A5_M1CLK_1-PadN17)") (class "Default")
      (node (ref "U1") (pin "N17") (pinfunction "IO_L38P_A5_M1CLK_1_N17") (pintype "passive+no_connect"))
    )
    (net (code "179") (name "unconnected-(U1B-IO_L39N_M1ODT_1-PadR24)") (class "Default")
      (node (ref "U1") (pin "R24") (pinfunction "IO_L39N_M1ODT_1_R24") (pintype "passive+no_connect"))
    )
    (net (code "180") (name "unconnected-(U1B-IO_L39P_M1A3_1-PadR23)") (class "Default")
      (node (ref "U1") (pin "R23") (pinfunction "IO_L39P_M1A3_1_R23") (pintype "passive+no_connect"))
    )
    (net (code "181") (name "unconnected-(U1B-IO_L40N_GCLK10_M1A6_1-PadM21)") (class "Default")
      (node (ref "U1") (pin "M21") (pinfunction "IO_L40N_GCLK10_M1A6_1_M21") (pintype "passive+no_connect"))
    )
    (net (code "182") (name "unconnected-(U1B-IO_L40P_GCLK11_M1A5_1-PadN20)") (class "Default")
      (node (ref "U1") (pin "N20") (pinfunction "IO_L40P_GCLK11_M1A5_1_N20") (pintype "passive+no_connect"))
    )
    (net (code "183") (name "unconnected-(U1B-IO_L41N_GCLK8_M1CASN_1-PadP22)") (class "Default")
      (node (ref "U1") (pin "P22") (pinfunction "IO_L41N_GCLK8_M1CASN_1_P22") (pintype "passive+no_connect"))
    )
    (net (code "184") (name "unconnected-(U1B-IO_L41P_GCLK9_IRDY1_M1RASN_1-PadP21)") (class "Default")
      (node (ref "U1") (pin "P21") (pinfunction "IO_L41P_GCLK9_IRDY1_M1RASN_1_P21") (pintype "passive+no_connect"))
    )
    (net (code "185") (name "unconnected-(U1B-IO_L42N_GCLK6_TRDY1_M1LDM_1-PadW24)") (class "Default")
      (node (ref "U1") (pin "W24") (pinfunction "IO_L42N_GCLK6_TRDY1_M1LDM_1_W24") (pintype "passive+no_connect"))
    )
    (net (code "186") (name "unconnected-(U1B-IO_L42P_GCLK7_M1UDM_1-PadV23)") (class "Default")
      (node (ref "U1") (pin "V23") (pinfunction "IO_L42P_GCLK7_M1UDM_1_V23") (pintype "passive+no_connect"))
    )
    (net (code "187") (name "unconnected-(U1B-IO_L43N_GCLK4_M1DQ5_1-PadU26)") (class "Default")
      (node (ref "U1") (pin "U26") (pinfunction "IO_L43N_GCLK4_M1DQ5_1_U26") (pintype "passive+no_connect"))
    )
    (net (code "188") (name "unconnected-(U1B-IO_L43P_GCLK5_M1DQ4_1-PadU25)") (class "Default")
      (node (ref "U1") (pin "U25") (pinfunction "IO_L43P_GCLK5_M1DQ4_1_U25") (pintype "passive+no_connect"))
    )
    (net (code "189") (name "unconnected-(U1B-IO_L44N_A2_M1DQ7_1-PadW26)") (class "Default")
      (node (ref "U1") (pin "W26") (pinfunction "IO_L44N_A2_M1DQ7_1_W26") (pintype "passive+no_connect"))
    )
    (net (code "190") (name "unconnected-(U1B-IO_L44P_A3_M1DQ6_1-PadW25)") (class "Default")
      (node (ref "U1") (pin "W25") (pinfunction "IO_L44P_A3_M1DQ6_1_W25") (pintype "passive+no_connect"))
    )
    (net (code "191") (name "unconnected-(U1B-IO_L45N_A0_M1LDQSN_1-PadV26)") (class "Default")
      (node (ref "U1") (pin "V26") (pinfunction "IO_L45N_A0_M1LDQSN_1_V26") (pintype "passive+no_connect"))
    )
    (net (code "192") (name "unconnected-(U1B-IO_L45P_A1_M1LDQS_1-PadV24)") (class "Default")
      (node (ref "U1") (pin "V24") (pinfunction "IO_L45P_A1_M1LDQS_1_V24") (pintype "passive+no_connect"))
    )
    (net (code "193") (name "unconnected-(U1B-IO_L46N_FOE_B_M1DQ3_1-PadT26)") (class "Default")
      (node (ref "U1") (pin "T26") (pinfunction "IO_L46N_FOE_B_M1DQ3_1_T26") (pintype "passive+no_connect"))
    )
    (net (code "194") (name "unconnected-(U1B-IO_L46P_FCS_B_M1DQ2_1-PadT24)") (class "Default")
      (node (ref "U1") (pin "T24") (pinfunction "IO_L46P_FCS_B_M1DQ2_1_T24") (pintype "passive+no_connect"))
    )
    (net (code "195") (name "unconnected-(U1B-IO_L47N_LDC_M1DQ1_1-PadY26)") (class "Default")
      (node (ref "U1") (pin "Y26") (pinfunction "IO_L47N_LDC_M1DQ1_1_Y26") (pintype "passive+no_connect"))
    )
    (net (code "196") (name "unconnected-(U1B-IO_L47P_FWE_B_M1DQ0_1-PadY24)") (class "Default")
      (node (ref "U1") (pin "Y24") (pinfunction "IO_L47P_FWE_B_M1DQ0_1_Y24") (pintype "passive+no_connect"))
    )
    (net (code "197") (name "unconnected-(U1B-IO_L48N_M1DQ9_1-PadAD26)") (class "Default")
      (node (ref "U1") (pin "AD26") (pinfunction "IO_L48N_M1DQ9_1_AD26") (pintype "passive+no_connect"))
    )
    (net (code "198") (name "unconnected-(U1B-IO_L48P_HDC_M1DQ8_1-PadAD24)") (class "Default")
      (node (ref "U1") (pin "AD24") (pinfunction "IO_L48P_HDC_M1DQ8_1_AD24") (pintype "passive+no_connect"))
    )
    (net (code "199") (name "unconnected-(U1B-IO_L49N_M1DQ11_1-PadAB26)") (class "Default")
      (node (ref "U1") (pin "AB26") (pinfunction "IO_L49N_M1DQ11_1_AB26") (pintype "passive+no_connect"))
    )
    (net (code "200") (name "unconnected-(U1B-IO_L49P_M1DQ10_1-PadAB24)") (class "Default")
      (node (ref "U1") (pin "AB24") (pinfunction "IO_L49P_M1DQ10_1_AB24") (pintype "passive+no_connect"))
    )
    (net (code "201") (name "unconnected-(U1B-IO_L50N_M1UDQSN_1-PadAC26)") (class "Default")
      (node (ref "U1") (pin "AC26") (pinfunction "IO_L50N_M1UDQSN_1_AC26") (pintype "passive+no_connect"))
    )
    (net (code "202") (name "unconnected-(U1B-IO_L50P_M1UDQS_1-PadAC25)") (class "Default")
      (node (ref "U1") (pin "AC25") (pinfunction "IO_L50P_M1UDQS_1_AC25") (pintype "passive+no_connect"))
    )
    (net (code "203") (name "unconnected-(U1B-IO_L51N_M1DQ13_1-PadAA26)") (class "Default")
      (node (ref "U1") (pin "AA26") (pinfunction "IO_L51N_M1DQ13_1_AA26") (pintype "passive+no_connect"))
    )
    (net (code "204") (name "unconnected-(U1B-IO_L51P_M1DQ12_1-PadAA25)") (class "Default")
      (node (ref "U1") (pin "AA25") (pinfunction "IO_L51P_M1DQ12_1_AA25") (pintype "passive+no_connect"))
    )
    (net (code "205") (name "unconnected-(U1B-IO_L52N_M1DQ15_1-PadAE26)") (class "Default")
      (node (ref "U1") (pin "AE26") (pinfunction "IO_L52N_M1DQ15_1_AE26") (pintype "passive+no_connect"))
    )
    (net (code "206") (name "unconnected-(U1B-IO_L52P_M1DQ14_1-PadAE25)") (class "Default")
      (node (ref "U1") (pin "AE25") (pinfunction "IO_L52P_M1DQ14_1_AE25") (pintype "passive+no_connect"))
    )
    (net (code "207") (name "unconnected-(U1B-IO_L53N_VREF_1-PadU24)") (class "Default")
      (node (ref "U1") (pin "U24") (pinfunction "IO_L53N_VREF_1_U24") (pintype "passive+no_connect"))
    )
    (net (code "208") (name "unconnected-(U1B-IO_L53P_1-PadT23)") (class "Default")
      (node (ref "U1") (pin "T23") (pinfunction "IO_L53P_1_T23") (pintype "passive+no_connect"))
    )
    (net (code "209") (name "unconnected-(U1B-IO_L55N_1-PadR21)") (class "Default")
      (node (ref "U1") (pin "R21") (pinfunction "IO_L55N_1_R21") (pintype "passive+no_connect"))
    )
    (net (code "210") (name "unconnected-(U1B-IO_L55P_1-PadR22)") (class "Default")
      (node (ref "U1") (pin "R22") (pinfunction "IO_L55P_1_R22") (pintype "passive+no_connect"))
    )
    (net (code "211") (name "unconnected-(U1B-IO_L56N_1-PadP18)") (class "Default")
      (node (ref "U1") (pin "P18") (pinfunction "IO_L56N_1_P18") (pintype "passive+no_connect"))
    )
    (net (code "212") (name "unconnected-(U1B-IO_L56P_1-PadP17)") (class "Default")
      (node (ref "U1") (pin "P17") (pinfunction "IO_L56P_1_P17") (pintype "passive+no_connect"))
    )
    (net (code "213") (name "unconnected-(U1B-IO_L57N_1-PadR19)") (class "Default")
      (node (ref "U1") (pin "R19") (pinfunction "IO_L57N_1_R19") (pintype "passive+no_connect"))
    )
    (net (code "214") (name "unconnected-(U1B-IO_L57P_1-PadR20)") (class "Default")
      (node (ref "U1") (pin "R20") (pinfunction "IO_L57P_1_R20") (pintype "passive+no_connect"))
    )
    (net (code "215") (name "unconnected-(U1B-IO_L58N_1-PadR18)") (class "Default")
      (node (ref "U1") (pin "R18") (pinfunction "IO_L58N_1_R18") (pintype "passive+no_connect"))
    )
    (net (code "216") (name "unconnected-(U1B-IO_L58P_1-PadR17)") (class "Default")
      (node (ref "U1") (pin "R17") (pinfunction "IO_L58P_1_R17") (pintype "passive+no_connect"))
    )
    (net (code "217") (name "unconnected-(U1B-IO_L59N_1-PadU23)") (class "Default")
      (node (ref "U1") (pin "U23") (pinfunction "IO_L59N_1_U23") (pintype "passive+no_connect"))
    )
    (net (code "218") (name "unconnected-(U1B-IO_L59P_1-PadT22)") (class "Default")
      (node (ref "U1") (pin "T22") (pinfunction "IO_L59P_1_T22") (pintype "passive+no_connect"))
    )
    (net (code "219") (name "unconnected-(U1B-IO_L60N_1-PadT19)") (class "Default")
      (node (ref "U1") (pin "T19") (pinfunction "IO_L60N_1_T19") (pintype "passive+no_connect"))
    )
    (net (code "220") (name "unconnected-(U1B-IO_L60P_1-PadT18)") (class "Default")
      (node (ref "U1") (pin "T18") (pinfunction "IO_L60P_1_T18") (pintype "passive+no_connect"))
    )
    (net (code "221") (name "unconnected-(U1B-IO_L61N_1-PadU22)") (class "Default")
      (node (ref "U1") (pin "U22") (pinfunction "IO_L61N_1_U22") (pintype "passive+no_connect"))
    )
    (net (code "222") (name "unconnected-(U1B-IO_L61P_1-PadU21)") (class "Default")
      (node (ref "U1") (pin "U21") (pinfunction "IO_L61P_1_U21") (pintype "passive+no_connect"))
    )
    (net (code "223") (name "unconnected-(U1B-IO_L62N_1-PadV17)") (class "Default")
      (node (ref "U1") (pin "V17") (pinfunction "IO_L62N_1_V17") (pintype "passive+no_connect"))
    )
    (net (code "224") (name "unconnected-(U1B-IO_L62P_1-PadU17)") (class "Default")
      (node (ref "U1") (pin "U17") (pinfunction "IO_L62P_1_U17") (pintype "passive+no_connect"))
    )
    (net (code "225") (name "unconnected-(U1B-IO_L63N_1-PadAA24)") (class "Default")
      (node (ref "U1") (pin "AA24") (pinfunction "IO_L63N_1_AA24") (pintype "passive+no_connect"))
    )
    (net (code "226") (name "unconnected-(U1B-IO_L63P_1-PadAA23)") (class "Default")
      (node (ref "U1") (pin "AA23") (pinfunction "IO_L63P_1_AA23") (pintype "passive+no_connect"))
    )
    (net (code "227") (name "unconnected-(U1B-IO_L64N_1-PadU20)") (class "Default")
      (node (ref "U1") (pin "U20") (pinfunction "IO_L64N_1_U20") (pintype "passive+no_connect"))
    )
    (net (code "228") (name "unconnected-(U1B-IO_L64P_1-PadT20)") (class "Default")
      (node (ref "U1") (pin "T20") (pinfunction "IO_L64P_1_T20") (pintype "passive+no_connect"))
    )
    (net (code "229") (name "unconnected-(U1B-IO_L65N_1-PadAC24)") (class "Default")
      (node (ref "U1") (pin "AC24") (pinfunction "IO_L65N_1_AC24") (pintype "passive+no_connect"))
    )
    (net (code "230") (name "unconnected-(U1B-IO_L65P_1-PadAC23)") (class "Default")
      (node (ref "U1") (pin "AC23") (pinfunction "IO_L65P_1_AC23") (pintype "passive+no_connect"))
    )
    (net (code "231") (name "unconnected-(U1B-IO_L66N_1-PadV19)") (class "Default")
      (node (ref "U1") (pin "V19") (pinfunction "IO_L66N_1_V19") (pintype "passive+no_connect"))
    )
    (net (code "232") (name "unconnected-(U1B-IO_L66P_1-PadV18)") (class "Default")
      (node (ref "U1") (pin "V18") (pinfunction "IO_L66P_1_V18") (pintype "passive+no_connect"))
    )
    (net (code "233") (name "unconnected-(U1B-IO_L67N_1-PadAF25)") (class "Default")
      (node (ref "U1") (pin "AF25") (pinfunction "IO_L67N_1_AF25") (pintype "passive+no_connect"))
    )
    (net (code "234") (name "unconnected-(U1B-IO_L67P_1-PadAE24)") (class "Default")
      (node (ref "U1") (pin "AE24") (pinfunction "IO_L67P_1_AE24") (pintype "passive+no_connect"))
    )
    (net (code "235") (name "unconnected-(U1B-IO_L68N_1-PadW19)") (class "Default")
      (node (ref "U1") (pin "W19") (pinfunction "IO_L68N_1_W19") (pintype "passive+no_connect"))
    )
    (net (code "236") (name "unconnected-(U1B-IO_L68P_1-PadW18)") (class "Default")
      (node (ref "U1") (pin "W18") (pinfunction "IO_L68P_1_W18") (pintype "passive+no_connect"))
    )
    (net (code "237") (name "unconnected-(U1B-IO_L69N_VREF_1-PadAB22)") (class "Default")
      (node (ref "U1") (pin "AB22") (pinfunction "IO_L69N_VREF_1_AB22") (pintype "passive+no_connect"))
    )
    (net (code "238") (name "unconnected-(U1B-IO_L69P_1-PadAB21)") (class "Default")
      (node (ref "U1") (pin "AB21") (pinfunction "IO_L69P_1_AB21") (pintype "passive+no_connect"))
    )
    (net (code "239") (name "unconnected-(U1B-IO_L70N_1-PadV20)") (class "Default")
      (node (ref "U1") (pin "V20") (pinfunction "IO_L70N_1_V20") (pintype "passive+no_connect"))
    )
    (net (code "240") (name "unconnected-(U1B-IO_L70P_1-PadU19)") (class "Default")
      (node (ref "U1") (pin "U19") (pinfunction "IO_L70P_1_U19") (pintype "passive+no_connect"))
    )
    (net (code "241") (name "unconnected-(U1B-IO_L71N_1-PadW22)") (class "Default")
      (node (ref "U1") (pin "W22") (pinfunction "IO_L71N_1_W22") (pintype "passive+no_connect"))
    )
    (net (code "242") (name "unconnected-(U1B-IO_L71P_1-PadV22)") (class "Default")
      (node (ref "U1") (pin "V22") (pinfunction "IO_L71P_1_V22") (pintype "passive+no_connect"))
    )
    (net (code "243") (name "unconnected-(U1B-IO_L72N_1-PadY21)") (class "Default")
      (node (ref "U1") (pin "Y21") (pinfunction "IO_L72N_1_Y21") (pintype "passive+no_connect"))
    )
    (net (code "244") (name "unconnected-(U1B-IO_L72P_1-PadY20)") (class "Default")
      (node (ref "U1") (pin "Y20") (pinfunction "IO_L72P_1_Y20") (pintype "passive+no_connect"))
    )
    (net (code "245") (name "unconnected-(U1B-IO_L73N_1-PadAA22)") (class "Default")
      (node (ref "U1") (pin "AA22") (pinfunction "IO_L73N_1_AA22") (pintype "passive+no_connect"))
    )
    (net (code "246") (name "unconnected-(U1B-IO_L73P_1-PadY22)") (class "Default")
      (node (ref "U1") (pin "Y22") (pinfunction "IO_L73P_1_Y22") (pintype "passive+no_connect"))
    )
    (net (code "247") (name "unconnected-(U1B-IO_L74N_DOUT_BUSY_1-PadAF24)") (class "Default")
      (node (ref "U1") (pin "AF24") (pinfunction "IO_L74N_DOUT_BUSY_1_AF24") (pintype "passive+no_connect"))
    )
    (net (code "248") (name "unconnected-(U1B-IO_L74P_AWAKE_1-PadAE23)") (class "Default")
      (node (ref "U1") (pin "AE23") (pinfunction "IO_L74P_AWAKE_1_AE23") (pintype "passive+no_connect"))
    )
    (net (code "249") (name "unconnected-(U1F-IO_L2N_M5A14_5-PadG21)") (class "Default")
      (node (ref "U1") (pin "G21") (pinfunction "IO_L2N_M5A14_5_G21") (pintype "passive+no_connect"))
    )
    (net (code "250") (name "unconnected-(U1F-IO_L26P_5-PadL20)") (class "Default")
      (node (ref "U1") (pin "L20") (pinfunction "IO_L26P_5_L20") (pintype "passive+no_connect"))
    )
    (net (code "251") (name "unconnected-(U1F-IO_L27N_5-PadJ20)") (class "Default")
      (node (ref "U1") (pin "J20") (pinfunction "IO_L27N_5_J20") (pintype "passive+no_connect"))
    )
    (net (code "252") (name "unconnected-(U1F-IO_L27P_5-PadH19)") (class "Default")
      (node (ref "U1") (pin "H19") (pinfunction "IO_L27P_5_H19") (pintype "passive+no_connect"))
    )
  )
)
